# deepak_sch_FInal.net
KiCad netlist of a schematic drawn in EAGLE
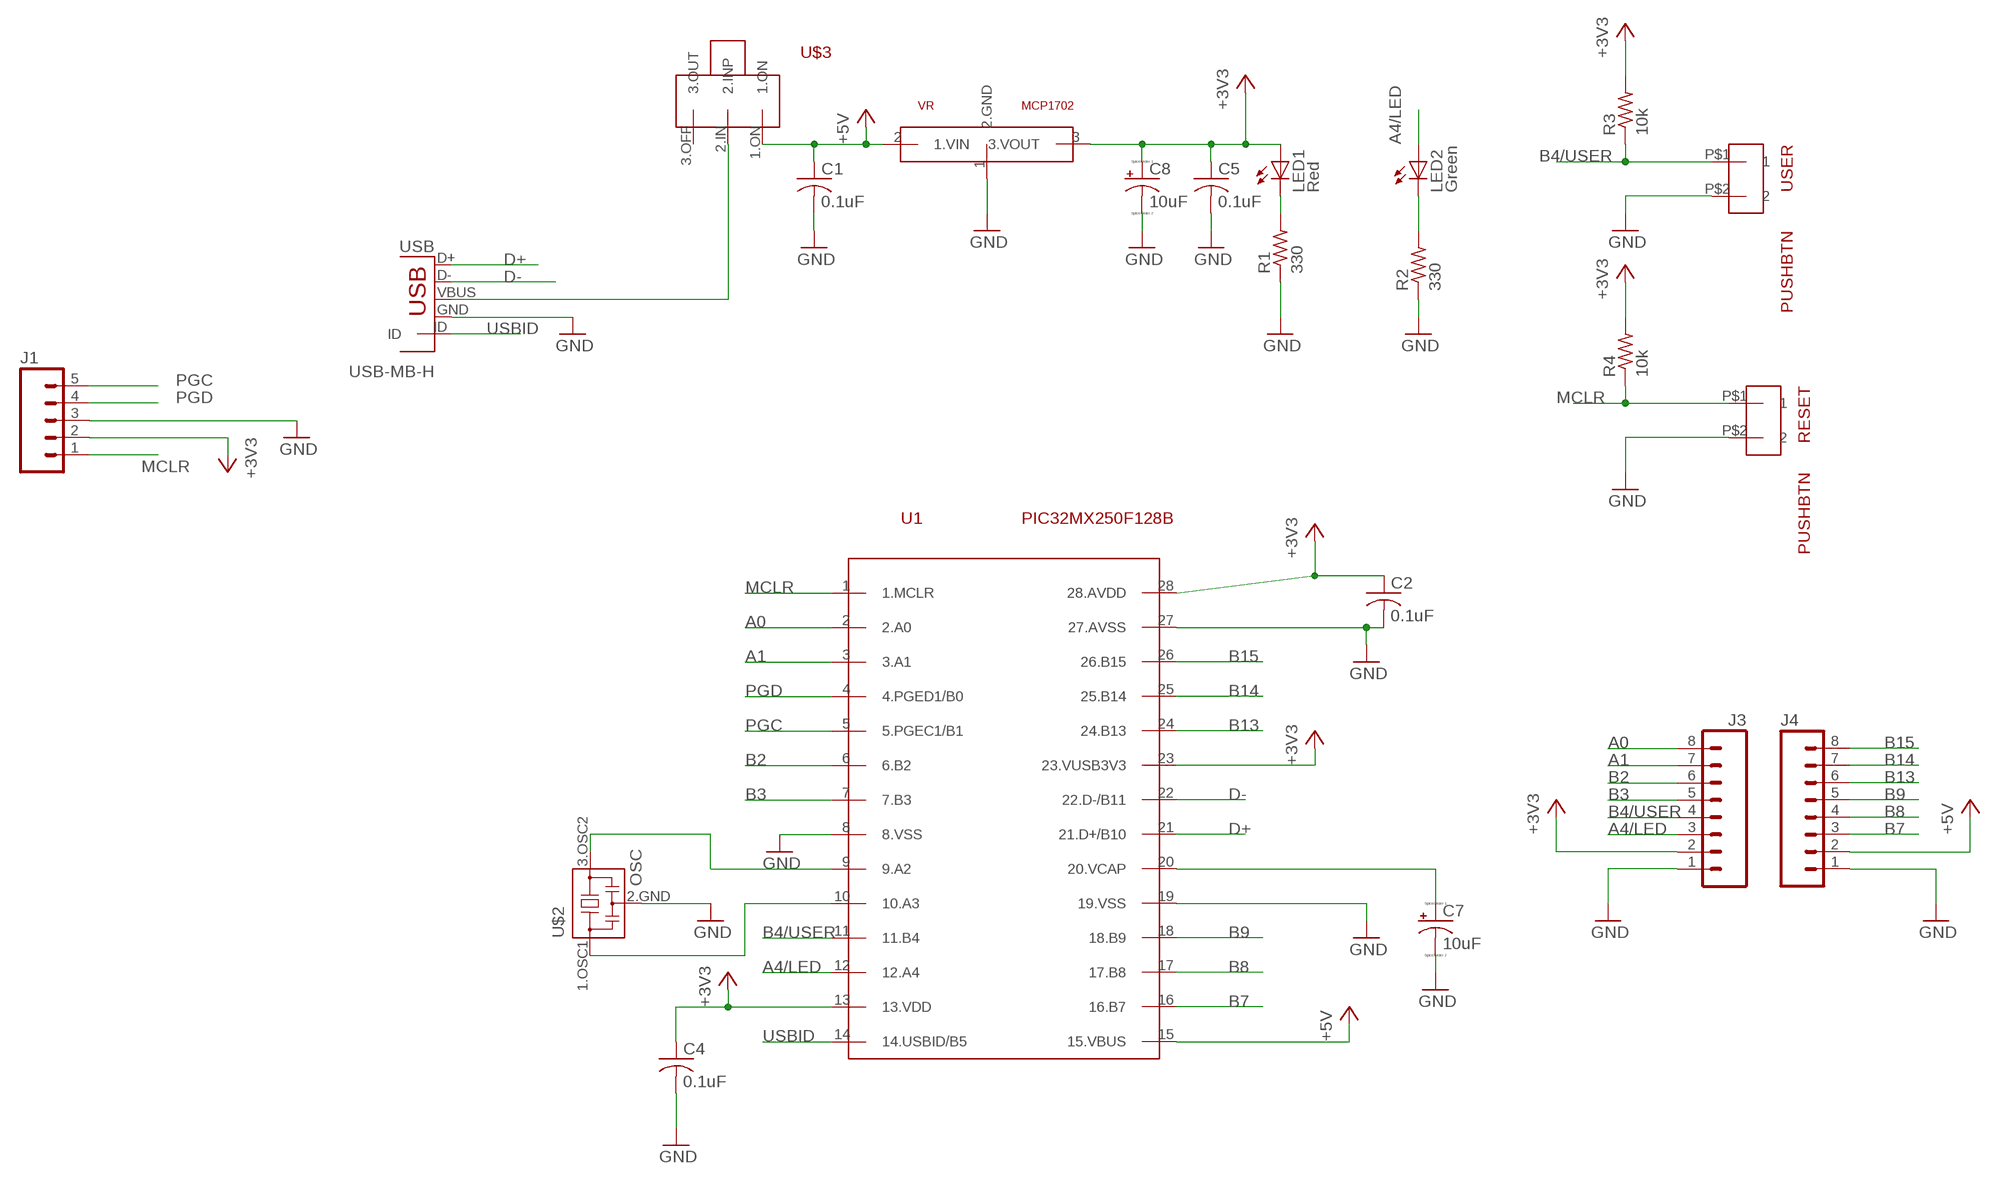
[diagram p0: schematic, sheet 1]

(export (version "E")
  (design (tool "Eeschema 10.0.6"))
  (components
    (comp (ref "C1")
      (value "0.1uF")
      (footprint "eagle-import:C025-024X044")
      (libsource (lib "eagle-import") (part "C-US025-024X044"))
    )
    (comp (ref "C2")
      (value "0.1uF")
      (footprint "eagle-import:C025-024X044")
      (libsource (lib "eagle-import") (part "C-US025-024X044"))
    )
    (comp (ref "C4")
      (value "0.1uF")
      (footprint "eagle-import:C025-024X044")
      (libsource (lib "eagle-import") (part "C-US025-024X044"))
    )
    (comp (ref "C5")
      (value "0.1uF")
      (footprint "eagle-import:C025-024X044")
      (libsource (lib "eagle-import") (part "C-US025-024X044"))
    )
    (comp (ref "C7")
      (value "10uF")
      (footprint "eagle-import:B45181A")
      (libsource (lib "eagle-import") (part "CPOL-USB45181A"))
    )
    (comp (ref "C8")
      (value "10uF")
      (footprint "eagle-import:B45181A")
      (libsource (lib "eagle-import") (part "CPOL-USB45181A"))
    )
    (comp (ref "J1")
      (value "M05PTH")
      (footprint "eagle-import:1X05")
      (libsource (lib "eagle-import") (part "M05PTH"))
    )
    (comp (ref "J3")
      (value "M08")
      (footprint "eagle-import:1X08_ROUND")
      (libsource (lib "eagle-import") (part "M08"))
    )
    (comp (ref "J4")
      (value "M08")
      (footprint "eagle-import:1X08_ROUND")
      (libsource (lib "eagle-import") (part "M08"))
    )
    (comp (ref "LED1")
      (value "Red")
      (footprint "eagle-import:LED3MM")
      (libsource (lib "eagle-import") (part "LED3MM"))
    )
    (comp (ref "LED2")
      (value "Green")
      (footprint "eagle-import:LED3MM")
      (libsource (lib "eagle-import") (part "LED3MM"))
    )
    (comp (ref "R1")
      (value "330")
      (footprint "eagle-import:0207_10")
      (libsource (lib "eagle-import") (part "R-US_0207/10"))
    )
    (comp (ref "R2")
      (value "330")
      (footprint "eagle-import:0207_10")
      (libsource (lib "eagle-import") (part "R-US_0207/10"))
    )
    (comp (ref "R3")
      (value "10k")
      (footprint "eagle-import:0207_10")
      (libsource (lib "eagle-import") (part "R-US_0207/10"))
    )
    (comp (ref "R4")
      (value "10k")
      (footprint "eagle-import:0207_10")
      (libsource (lib "eagle-import") (part "R-US_0207/10"))
    )
    (comp (ref "RESET")
      (value "PUSHBTN")
      (footprint "eagle-import:PUSHBTN")
      (libsource (lib "eagle-import") (part "PUSHBTN"))
    )
    (comp (ref "U$2")
      (value "OSC")
      (footprint "eagle-import:OSC")
      (libsource (lib "eagle-import") (part "OSC"))
    )
    (comp (ref "U$3")
      (value "SLIDESWITCH")
      (footprint "eagle-import:SLIDESWITCH")
      (libsource (lib "eagle-import") (part "SLIDESWITCH"))
    )
    (comp (ref "U1")
      (value "PIC32MX250F128B")
      (footprint "eagle-import:DIL28-3")
      (libsource (lib "eagle-import") (part "PIC32MX250F128B"))
    )
    (comp (ref "USB")
      (value "USB-MB-H")
      (footprint "eagle-import:USB-MB-H")
      (libsource (lib "eagle-import") (part "USB-MB-H"))
    )
    (comp (ref "USER")
      (value "PUSHBTN")
      (footprint "eagle-import:PUSHBTN")
      (libsource (lib "eagle-import") (part "PUSHBTN"))
    )
    (comp (ref "VR")
      (value "MCP1702")
      (footprint "eagle-import:TO92")
      (libsource (lib "eagle-import") (part "MCP1702"))
    )
  )
  (nets
    (net (code "1") (name "+3V3") (class "Default")
      (node (ref "C2") (pin "1") (pinfunction "1_1") (pintype "passive"))
      (node (ref "C4") (pin "1") (pinfunction "1_1") (pintype "passive"))
      (node (ref "C5") (pin "1") (pinfunction "1_1") (pintype "passive"))
      (node (ref "C8") (pin "+") (pinfunction "+_+") (pintype "passive"))
      (node (ref "J1") (pin "2") (pinfunction "2_2") (pintype "passive"))
      (node (ref "J3") (pin "2") (pinfunction "2_2") (pintype "passive"))
      (node (ref "LED1") (pin "A") (pinfunction "A_A") (pintype "passive"))
      (node (ref "R3") (pin "2") (pinfunction "2_2") (pintype "passive"))
      (node (ref "R4") (pin "2") (pinfunction "2_2") (pintype "passive"))
      (node (ref "U1") (pin "13") (pinfunction "13.VDD_13") (pintype "bidirectional"))
      (node (ref "U1") (pin "23") (pinfunction "23.VUSB3V3_23") (pintype "bidirectional"))
      (node (ref "U1") (pin "28") (pinfunction "28.AVDD_28") (pintype "bidirectional"))
      (node (ref "VR") (pin "3") (pinfunction "3.VOUT_3") (pintype "bidirectional"))
    )
    (net (code "2") (name "+5V") (class "Default")
      (node (ref "C1") (pin "1") (pinfunction "1_1") (pintype "passive"))
      (node (ref "J4") (pin "2") (pinfunction "2_2") (pintype "passive"))
      (node (ref "U$3") (pin "1.ON") (pinfunction "1.ON_1.ON") (pintype "bidirectional"))
      (node (ref "U1") (pin "15") (pinfunction "15.VBUS_15") (pintype "bidirectional"))
      (node (ref "VR") (pin "2") (pinfunction "1.VIN_2") (pintype "bidirectional"))
    )
    (net (code "3") (name "/A0") (class "Default")
      (node (ref "J3") (pin "8") (pinfunction "8_8") (pintype "passive"))
      (node (ref "U1") (pin "2") (pinfunction "2.A0_2") (pintype "bidirectional"))
    )
    (net (code "4") (name "/A1") (class "Default")
      (node (ref "J3") (pin "7") (pinfunction "7_7") (pintype "passive"))
      (node (ref "U1") (pin "3") (pinfunction "3.A1_3") (pintype "bidirectional"))
    )
    (net (code "5") (name "/A4{slash}LED") (class "Default")
      (node (ref "J3") (pin "3") (pinfunction "3_3") (pintype "passive"))
      (node (ref "LED2") (pin "A") (pinfunction "A_A") (pintype "passive"))
      (node (ref "U1") (pin "12") (pinfunction "12.A4_12") (pintype "bidirectional"))
    )
    (net (code "6") (name "/B2") (class "Default")
      (node (ref "J3") (pin "6") (pinfunction "6_6") (pintype "passive"))
      (node (ref "U1") (pin "6") (pinfunction "6.B2_6") (pintype "bidirectional"))
    )
    (net (code "7") (name "/B3") (class "Default")
      (node (ref "J3") (pin "5") (pinfunction "5_5") (pintype "passive"))
      (node (ref "U1") (pin "7") (pinfunction "7.B3_7") (pintype "bidirectional"))
    )
    (net (code "8") (name "/B4{slash}USER") (class "Default")
      (node (ref "J3") (pin "4") (pinfunction "4_4") (pintype "passive"))
      (node (ref "R3") (pin "1") (pinfunction "1_1") (pintype "passive"))
      (node (ref "U1") (pin "11") (pinfunction "11.B4_11") (pintype "bidirectional"))
      (node (ref "USER") (pin "P$1") (pinfunction "1_P$1") (pintype "bidirectional"))
    )
    (net (code "9") (name "/B7") (class "Default")
      (node (ref "J4") (pin "3") (pinfunction "3_3") (pintype "passive"))
      (node (ref "U1") (pin "16") (pinfunction "16.B7_16") (pintype "bidirectional"))
    )
    (net (code "10") (name "/B8") (class "Default")
      (node (ref "J4") (pin "4") (pinfunction "4_4") (pintype "passive"))
      (node (ref "U1") (pin "17") (pinfunction "17.B8_17") (pintype "bidirectional"))
    )
    (net (code "11") (name "/B9") (class "Default")
      (node (ref "J4") (pin "5") (pinfunction "5_5") (pintype "passive"))
      (node (ref "U1") (pin "18") (pinfunction "18.B9_18") (pintype "bidirectional"))
    )
    (net (code "12") (name "/B13") (class "Default")
      (node (ref "J4") (pin "6") (pinfunction "6_6") (pintype "passive"))
      (node (ref "U1") (pin "24") (pinfunction "24.B13_24") (pintype "bidirectional"))
    )
    (net (code "13") (name "/B14") (class "Default")
      (node (ref "J4") (pin "7") (pinfunction "7_7") (pintype "passive"))
      (node (ref "U1") (pin "25") (pinfunction "25.B14_25") (pintype "bidirectional"))
    )
    (net (code "14") (name "/B15") (class "Default")
      (node (ref "J4") (pin "8") (pinfunction "8_8") (pintype "passive"))
      (node (ref "U1") (pin "26") (pinfunction "26.B15_26") (pintype "bidirectional"))
    )
    (net (code "15") (name "/D+") (class "Default")
      (node (ref "U1") (pin "21") (pinfunction "21.D+/B10_21") (pintype "bidirectional"))
      (node (ref "USB") (pin "D+") (pinfunction "D+_D+") (pintype "bidirectional"))
    )
    (net (code "16") (name "/D-") (class "Default")
      (node (ref "U1") (pin "22") (pinfunction "22.D-/B11_22") (pintype "bidirectional"))
      (node (ref "USB") (pin "D-") (pinfunction "D-_D-") (pintype "bidirectional"))
    )
    (net (code "17") (name "/MCLR") (class "Default")
      (node (ref "J1") (pin "1") (pinfunction "1_1") (pintype "passive"))
      (node (ref "R4") (pin "1") (pinfunction "1_1") (pintype "passive"))
      (node (ref "RESET") (pin "P$1") (pinfunction "1_P$1") (pintype "bidirectional"))
      (node (ref "U1") (pin "1") (pinfunction "1.MCLR_1") (pintype "bidirectional"))
    )
    (net (code "18") (name "/PGC") (class "Default")
      (node (ref "J1") (pin "5") (pinfunction "5_5") (pintype "passive"))
      (node (ref "U1") (pin "5") (pinfunction "5.PGEC1/B1_5") (pintype "bidirectional"))
    )
    (net (code "19") (name "/PGD") (class "Default")
      (node (ref "J1") (pin "4") (pinfunction "4_4") (pintype "passive"))
      (node (ref "U1") (pin "4") (pinfunction "4.PGED1/B0_4") (pintype "bidirectional"))
    )
    (net (code "20") (name "/USBID") (class "Default")
      (node (ref "U1") (pin "14") (pinfunction "14.USBID/B5_14") (pintype "bidirectional"))
      (node (ref "USB") (pin "ID") (pinfunction "ID_ID") (pintype "bidirectional"))
    )
    (net (code "21") (name "GND") (class "Default")
      (node (ref "C1") (pin "2") (pinfunction "2_2") (pintype "passive"))
      (node (ref "C2") (pin "2") (pinfunction "2_2") (pintype "passive"))
      (node (ref "C4") (pin "2") (pinfunction "2_2") (pintype "passive"))
      (node (ref "C5") (pin "2") (pinfunction "2_2") (pintype "passive"))
      (node (ref "C7") (pin "-") (pinfunction "-_-") (pintype "passive"))
      (node (ref "C8") (pin "-") (pinfunction "-_-") (pintype "passive"))
      (node (ref "J1") (pin "3") (pinfunction "3_3") (pintype "passive"))
      (node (ref "J3") (pin "1") (pinfunction "1_1") (pintype "passive"))
      (node (ref "J4") (pin "1") (pinfunction "1_1") (pintype "passive"))
      (node (ref "R1") (pin "1") (pinfunction "1_1") (pintype "passive"))
      (node (ref "R2") (pin "1") (pinfunction "1_1") (pintype "passive"))
      (node (ref "RESET") (pin "P$2") (pinfunction "2_P$2") (pintype "bidirectional"))
      (node (ref "U$2") (pin "2.GND") (pinfunction "2_2.GND") (pintype "passive"))
      (node (ref "U1") (pin "19") (pinfunction "19.VSS_19") (pintype "bidirectional"))
      (node (ref "U1") (pin "27") (pinfunction "27.AVSS_27") (pintype "bidirectional"))
      (node (ref "U1") (pin "8") (pinfunction "8.VSS_8") (pintype "bidirectional"))
      (node (ref "USB") (pin "GND") (pinfunction "GND_GND") (pintype "bidirectional"))
      (node (ref "USER") (pin "P$2") (pinfunction "2_P$2") (pintype "bidirectional"))
      (node (ref "VR") (pin "1") (pinfunction "2.GND_1") (pintype "bidirectional"))
    )
    (net (code "22") (name "Net-(LED1-C)") (class "Default")
      (node (ref "LED1") (pin "K") (pinfunction "C_K") (pintype "passive"))
      (node (ref "R1") (pin "2") (pinfunction "2_2") (pintype "passive"))
    )
    (net (code "23") (name "Net-(LED2-C)") (class "Default")
      (node (ref "LED2") (pin "K") (pinfunction "C_K") (pintype "passive"))
      (node (ref "R2") (pin "2") (pinfunction "2_2") (pintype "passive"))
    )
    (net (code "24") (name "Net-(U$2-1)") (class "Default")
      (node (ref "U$2") (pin "1.OSC1") (pinfunction "1_1.OSC1") (pintype "passive"))
      (node (ref "U1") (pin "10") (pinfunction "10.A3_10") (pintype "bidirectional"))
    )
    (net (code "25") (name "Net-(U$2-3)") (class "Default")
      (node (ref "U$2") (pin "3.OSC2") (pinfunction "3_3.OSC2") (pintype "passive"))
      (node (ref "U1") (pin "9") (pinfunction "9.A2_9") (pintype "bidirectional"))
    )
    (net (code "26") (name "Net-(U$3-2.INP)") (class "Default")
      (node (ref "U$3") (pin "2.IN") (pinfunction "2.INP_2.IN") (pintype "bidirectional"))
      (node (ref "USB") (pin "VBUS") (pinfunction "VBUS_VBUS") (pintype "bidirectional"))
    )
    (net (code "27") (name "Net-(U1-20.VCAP)") (class "Default")
      (node (ref "C7") (pin "+") (pinfunction "+_+") (pintype "passive"))
      (node (ref "U1") (pin "20") (pinfunction "20.VCAP_20") (pintype "bidirectional"))
    )
    (net (code "28") (name "unconnected-(U$3-3.OUT-Pad3.OFF)") (class "Default")
      (node (ref "U$3") (pin "3.OFF") (pinfunction "3.OUT_3.OFF") (pintype "bidirectional"))
    )
  )
)
